# main.net
KiCad netlist of a schematic drawn in Altium Designer
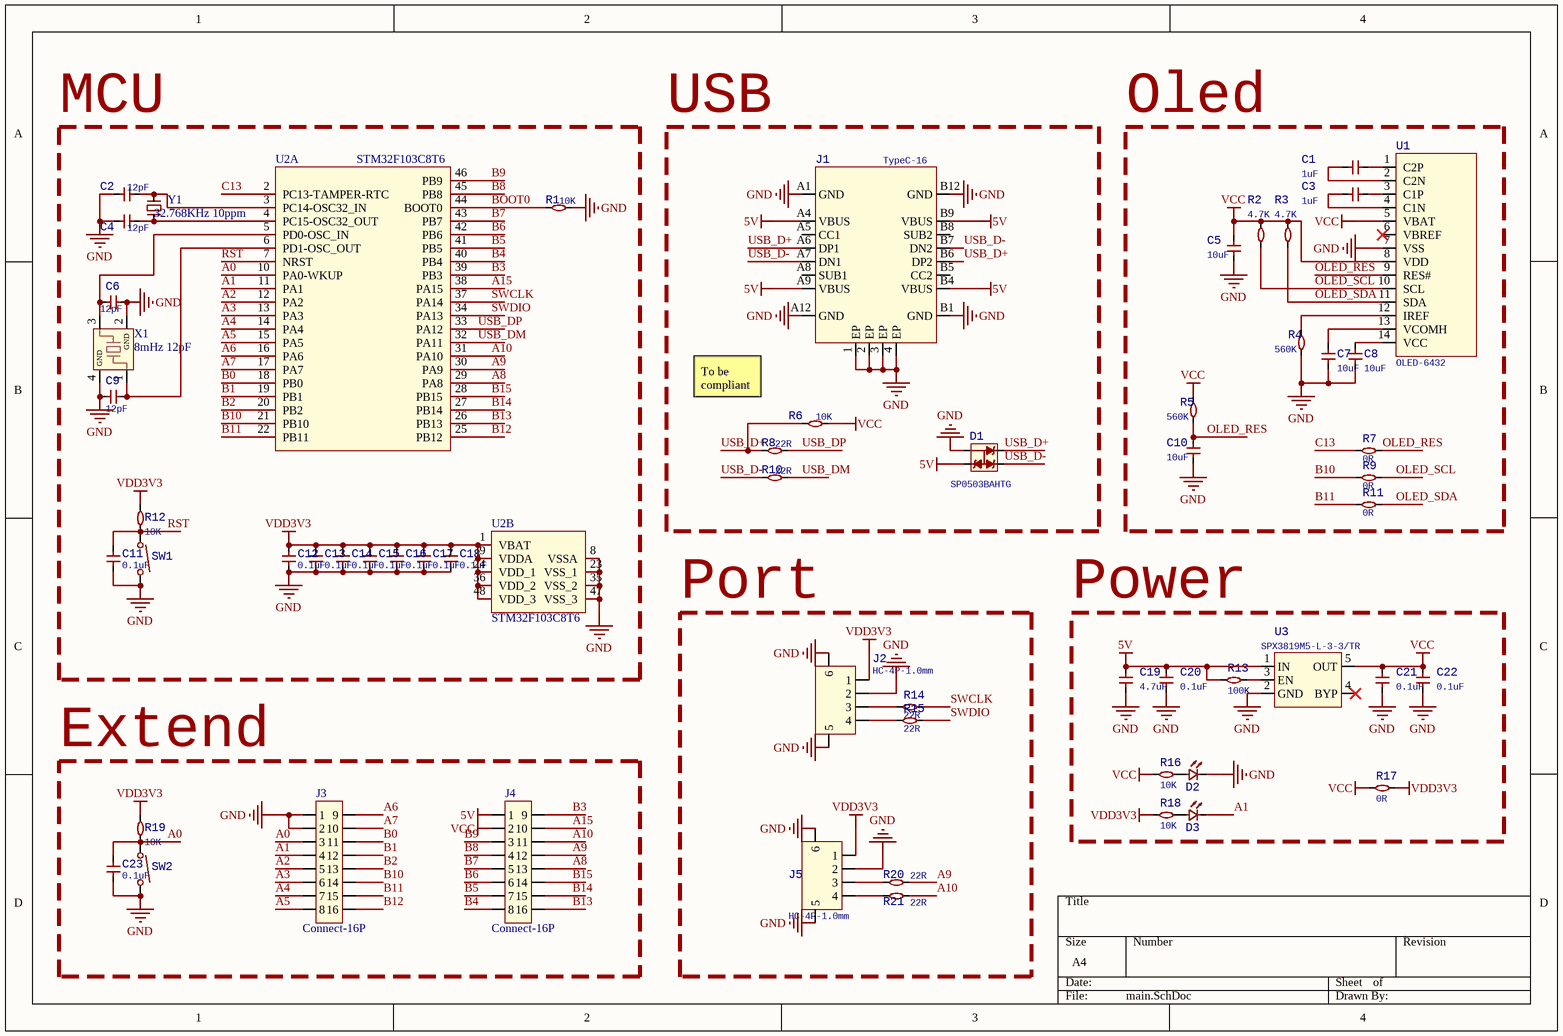
[diagram p0: main.SchDoc]

(export (version "E")
  (design (tool "Eeschema 10.0.6"))
  (components
    (comp (ref "C1")
      (value "1uF")
      (footprint "C0402")
      (description "贴片电容")
      (fields
        (field (name "MANUFACTURER") "SAMSUNG(三星)")
        (field (name "MANUFACTURER PART") "CL05A105KP5NNND")
      )
      (libsource (lib "schLibrary") (part "CAP"))
    )
    (comp (ref "C2")
      (value "12pF")
      (footprint "C0402")
      (description "贴片电容")
      (fields
        (field (name "MANUFACTURER") "SAMSUNG(三星)")
        (field (name "MANUFACTURER PART") "CL05A105KP5NNND")
      )
      (libsource (lib "schLibrary") (part "CAP"))
    )
    (comp (ref "C3")
      (value "1uF")
      (footprint "C0402")
      (description "贴片电容")
      (fields
        (field (name "MANUFACTURER") "SAMSUNG(三星)")
        (field (name "MANUFACTURER PART") "CL05A105KP5NNND")
      )
      (libsource (lib "schLibrary") (part "CAP"))
    )
    (comp (ref "C4")
      (value "12pF")
      (footprint "C0402")
      (description "贴片电容")
      (fields
        (field (name "MANUFACTURER") "SAMSUNG(三星)")
        (field (name "MANUFACTURER PART") "CL05A105KP5NNND")
      )
      (libsource (lib "schLibrary") (part "CAP"))
    )
    (comp (ref "C5")
      (value "10uF")
      (footprint "C0402")
      (description "贴片电容")
      (fields
        (field (name "MANUFACTURER") "SAMSUNG(三星)")
        (field (name "MANUFACTURER PART") "CL05A105KP5NNND")
      )
      (libsource (lib "schLibrary") (part "CAP"))
    )
    (comp (ref "C6")
      (value "12pF")
      (footprint "C0402")
      (description "贴片电容")
      (fields
        (field (name "MANUFACTURER") "SAMSUNG(三星)")
        (field (name "MANUFACTURER PART") "CL05A105KP5NNND")
      )
      (libsource (lib "schLibrary") (part "CAP"))
    )
    (comp (ref "C7")
      (value "10uF")
      (footprint "C0402")
      (description "贴片电容")
      (fields
        (field (name "MANUFACTURER") "SAMSUNG(三星)")
        (field (name "MANUFACTURER PART") "CL05A105KP5NNND")
      )
      (libsource (lib "schLibrary") (part "CAP"))
    )
    (comp (ref "C8")
      (value "10uF")
      (footprint "C0402")
      (description "贴片电容")
      (fields
        (field (name "MANUFACTURER") "SAMSUNG(三星)")
        (field (name "MANUFACTURER PART") "CL05A105KP5NNND")
      )
      (libsource (lib "schLibrary") (part "CAP"))
    )
    (comp (ref "C9")
      (value "12pF")
      (footprint "C0402")
      (description "贴片电容")
      (fields
        (field (name "MANUFACTURER") "SAMSUNG(三星)")
        (field (name "MANUFACTURER PART") "CL05A105KP5NNND")
      )
      (libsource (lib "schLibrary") (part "CAP"))
    )
    (comp (ref "C10")
      (value "10uF")
      (footprint "C0402")
      (description "贴片电容")
      (fields
        (field (name "MANUFACTURER") "SAMSUNG(三星)")
        (field (name "MANUFACTURER PART") "CL05A105KP5NNND")
      )
      (libsource (lib "schLibrary") (part "CAP"))
    )
    (comp (ref "C11")
      (value "0.1uF")
      (footprint "C0402")
      (description "贴片电容")
      (fields
        (field (name "MANUFACTURER") "SAMSUNG(三星)")
        (field (name "MANUFACTURER PART") "CL05A105KP5NNND")
      )
      (libsource (lib "schLibrary") (part "CAP"))
    )
    (comp (ref "C12")
      (value "0.1uF")
      (footprint "C0402")
      (description "贴片电容")
      (fields
        (field (name "MANUFACTURER") "SAMSUNG(三星)")
        (field (name "MANUFACTURER PART") "CL05A105KP5NNND")
      )
      (libsource (lib "schLibrary") (part "CAP"))
    )
    (comp (ref "C13")
      (value "0.1uF")
      (footprint "C0402")
      (description "贴片电容")
      (fields
        (field (name "MANUFACTURER") "SAMSUNG(三星)")
        (field (name "MANUFACTURER PART") "CL05A105KP5NNND")
      )
      (libsource (lib "schLibrary") (part "CAP"))
    )
    (comp (ref "C14")
      (value "0.1uF")
      (footprint "C0402")
      (description "贴片电容")
      (fields
        (field (name "MANUFACTURER") "SAMSUNG(三星)")
        (field (name "MANUFACTURER PART") "CL05A105KP5NNND")
      )
      (libsource (lib "schLibrary") (part "CAP"))
    )
    (comp (ref "C15")
      (value "0.1uF")
      (footprint "C0402")
      (description "贴片电容")
      (fields
        (field (name "MANUFACTURER") "SAMSUNG(三星)")
        (field (name "MANUFACTURER PART") "CL05A105KP5NNND")
      )
      (libsource (lib "schLibrary") (part "CAP"))
    )
    (comp (ref "C16")
      (value "0.1uF")
      (footprint "C0402")
      (description "贴片电容")
      (fields
        (field (name "MANUFACTURER") "SAMSUNG(三星)")
        (field (name "MANUFACTURER PART") "CL05A105KP5NNND")
      )
      (libsource (lib "schLibrary") (part "CAP"))
    )
    (comp (ref "C17")
      (value "0.1uF")
      (footprint "C0402")
      (description "贴片电容")
      (fields
        (field (name "MANUFACTURER") "SAMSUNG(三星)")
        (field (name "MANUFACTURER PART") "CL05A105KP5NNND")
      )
      (libsource (lib "schLibrary") (part "CAP"))
    )
    (comp (ref "C18")
      (value "0.1uF")
      (footprint "C0402")
      (description "贴片电容")
      (fields
        (field (name "MANUFACTURER") "SAMSUNG(三星)")
        (field (name "MANUFACTURER PART") "CL05A105KP5NNND")
      )
      (libsource (lib "schLibrary") (part "CAP"))
    )
    (comp (ref "C19")
      (value "4.7uF")
      (footprint "C0402")
      (description "贴片电容")
      (fields
        (field (name "MANUFACTURER") "SAMSUNG(三星)")
        (field (name "MANUFACTURER PART") "CL05A105KP5NNND")
      )
      (libsource (lib "schLibrary") (part "CAP"))
    )
    (comp (ref "C20")
      (value "0.1uF")
      (footprint "C0402")
      (description "贴片电容")
      (fields
        (field (name "MANUFACTURER") "SAMSUNG(三星)")
        (field (name "MANUFACTURER PART") "CL05A105KP5NNND")
      )
      (libsource (lib "schLibrary") (part "CAP"))
    )
    (comp (ref "C21")
      (value "0.1uF")
      (footprint "C0402")
      (description "贴片电容")
      (fields
        (field (name "MANUFACTURER") "SAMSUNG(三星)")
        (field (name "MANUFACTURER PART") "CL05A105KP5NNND")
      )
      (libsource (lib "schLibrary") (part "CAP"))
    )
    (comp (ref "C22")
      (value "0.1uF")
      (footprint "C0402")
      (description "贴片电容")
      (fields
        (field (name "MANUFACTURER") "SAMSUNG(三星)")
        (field (name "MANUFACTURER PART") "CL05A105KP5NNND")
      )
      (libsource (lib "schLibrary") (part "CAP"))
    )
    (comp (ref "C23")
      (value "0.1uF")
      (footprint "C0402")
      (description "贴片电容")
      (fields
        (field (name "MANUFACTURER") "SAMSUNG(三星)")
        (field (name "MANUFACTURER PART") "CL05A105KP5NNND")
      )
      (libsource (lib "schLibrary") (part "CAP"))
    )
    (comp (ref "D1")
      (value "SP0503BAHTG")
      (footprint "SOT-143")
      (description "USB-三组 瞬态移植二极管")
      (libsource (lib "schLibrary") (part "SP0503BAHTG"))
    )
    (comp (ref "D2")
      (value "LED")
      (footprint "LED-0402")
      (description "贴片发光二极管")
      (fields
        (field (name "MANUFACTURER") "SAMSUNG(三星)")
        (field (name "MANUFACTURER PART") "CL05A105KP5NNND")
      )
      (libsource (lib "schLibrary") (part "LED"))
    )
    (comp (ref "D3")
      (value "LED")
      (footprint "LED-0402")
      (description "贴片发光二极管")
      (fields
        (field (name "MANUFACTURER") "SAMSUNG(三星)")
        (field (name "MANUFACTURER PART") "CL05A105KP5NNND")
      )
      (libsource (lib "schLibrary") (part "LED"))
    )
    (comp (ref "J1")
      (value "TypeC-16")
      (footprint "USB-SMD_TYPE-C-16P")
      (description "Type-C母座; 触点数量:16")
      (fields
        (field (name "MANUFACTURER") "kinghelm(金航标)")
        (field (name "MANUFACTURER PART") "KH-TYPE-C-16P")
      )
      (libsource (lib "schLibrary") (part "TypeC-16P"))
    )
    (comp (ref "J2")
      (value "HC-4P-1.0mm")
      (footprint "SMD_4P_HC-1.0")
      (description "线对板连接器")
      (libsource (lib "schLibrary") (part "HC-4P-1.0mm"))
    )
    (comp (ref "J3")
      (value "Connect-16P")
      (footprint "PIN-16P")
      (description "通用连接器")
      (libsource (lib "schLibrary") (part "Connect-16P"))
    )
    (comp (ref "J4")
      (value "Connect-16P")
      (footprint "PIN-16P")
      (description "通用连接器")
      (libsource (lib "schLibrary") (part "Connect-16P"))
    )
    (comp (ref "J5")
      (value "HC-4P-1.0mm")
      (footprint "SMD_4P_HC-1.0")
      (description "线对板连接器")
      (libsource (lib "schLibrary") (part "HC-4P-1.0mm"))
    )
    (comp (ref "R1")
      (value "10K")
      (footprint "R0402")
      (description "贴片电阻")
      (fields
        (field (name "MANUFACTURER") "UNI-ROYAL(厚声)")
        (field (name "MANUFACTURER PART") "0402WGF1001TCE")
      )
      (libsource (lib "schLibrary") (part "RES"))
    )
    (comp (ref "R2")
      (value "4.7K")
      (footprint "R0402")
      (description "贴片电阻")
      (fields
        (field (name "MANUFACTURER") "UNI-ROYAL(厚声)")
        (field (name "MANUFACTURER PART") "0402WGF1001TCE")
      )
      (libsource (lib "schLibrary") (part "RES"))
    )
    (comp (ref "R3")
      (value "4.7K")
      (footprint "R0402")
      (description "贴片电阻")
      (fields
        (field (name "MANUFACTURER") "UNI-ROYAL(厚声)")
        (field (name "MANUFACTURER PART") "0402WGF1001TCE")
      )
      (libsource (lib "schLibrary") (part "RES"))
    )
    (comp (ref "R4")
      (value "560K")
      (footprint "R0402")
      (description "贴片电阻")
      (fields
        (field (name "MANUFACTURER") "UNI-ROYAL(厚声)")
        (field (name "MANUFACTURER PART") "0402WGF1001TCE")
      )
      (libsource (lib "schLibrary") (part "RES"))
    )
    (comp (ref "R5")
      (value "560K")
      (footprint "R0402")
      (description "贴片电阻")
      (fields
        (field (name "MANUFACTURER") "UNI-ROYAL(厚声)")
        (field (name "MANUFACTURER PART") "0402WGF1001TCE")
      )
      (libsource (lib "schLibrary") (part "RES"))
    )
    (comp (ref "R6")
      (value "10K")
      (footprint "R0402")
      (description "贴片电阻")
      (fields
        (field (name "MANUFACTURER") "UNI-ROYAL(厚声)")
        (field (name "MANUFACTURER PART") "0402WGF1001TCE")
      )
      (libsource (lib "schLibrary") (part "RES"))
    )
    (comp (ref "R7")
      (value "0R")
      (footprint "R0402")
      (description "贴片电阻")
      (fields
        (field (name "MANUFACTURER") "UNI-ROYAL(厚声)")
        (field (name "MANUFACTURER PART") "0402WGF1001TCE")
      )
      (libsource (lib "schLibrary") (part "RES"))
    )
    (comp (ref "R8")
      (value "22R")
      (footprint "R0402")
      (description "贴片电阻")
      (fields
        (field (name "MANUFACTURER") "UNI-ROYAL(厚声)")
        (field (name "MANUFACTURER PART") "0402WGF1001TCE")
      )
      (libsource (lib "schLibrary") (part "RES"))
    )
    (comp (ref "R9")
      (value "0R")
      (footprint "R0402")
      (description "贴片电阻")
      (fields
        (field (name "MANUFACTURER") "UNI-ROYAL(厚声)")
        (field (name "MANUFACTURER PART") "0402WGF1001TCE")
      )
      (libsource (lib "schLibrary") (part "RES"))
    )
    (comp (ref "R10")
      (value "22R")
      (footprint "R0402")
      (description "贴片电阻")
      (fields
        (field (name "MANUFACTURER") "UNI-ROYAL(厚声)")
        (field (name "MANUFACTURER PART") "0402WGF1001TCE")
      )
      (libsource (lib "schLibrary") (part "RES"))
    )
    (comp (ref "R11")
      (value "0R")
      (footprint "R0402")
      (description "贴片电阻")
      (fields
        (field (name "MANUFACTURER") "UNI-ROYAL(厚声)")
        (field (name "MANUFACTURER PART") "0402WGF1001TCE")
      )
      (libsource (lib "schLibrary") (part "RES"))
    )
    (comp (ref "R12")
      (value "10K")
      (footprint "R0402")
      (description "贴片电阻")
      (fields
        (field (name "MANUFACTURER") "UNI-ROYAL(厚声)")
        (field (name "MANUFACTURER PART") "0402WGF1001TCE")
      )
      (libsource (lib "schLibrary") (part "RES"))
    )
    (comp (ref "R13")
      (value "100K")
      (footprint "R0402")
      (description "贴片电阻")
      (fields
        (field (name "MANUFACTURER") "UNI-ROYAL(厚声)")
        (field (name "MANUFACTURER PART") "0402WGF1001TCE")
      )
      (libsource (lib "schLibrary") (part "RES"))
    )
    (comp (ref "R14")
      (value "22R")
      (footprint "R0402")
      (description "贴片电阻")
      (fields
        (field (name "MANUFACTURER") "UNI-ROYAL(厚声)")
        (field (name "MANUFACTURER PART") "0402WGF1001TCE")
      )
      (libsource (lib "schLibrary") (part "RES"))
    )
    (comp (ref "R15")
      (value "22R")
      (footprint "R0402")
      (description "贴片电阻")
      (fields
        (field (name "MANUFACTURER") "UNI-ROYAL(厚声)")
        (field (name "MANUFACTURER PART") "0402WGF1001TCE")
      )
      (libsource (lib "schLibrary") (part "RES"))
    )
    (comp (ref "R16")
      (value "10K")
      (footprint "R0402")
      (description "贴片电阻")
      (fields
        (field (name "MANUFACTURER") "UNI-ROYAL(厚声)")
        (field (name "MANUFACTURER PART") "0402WGF1001TCE")
      )
      (libsource (lib "schLibrary") (part "RES"))
    )
    (comp (ref "R17")
      (value "0R")
      (footprint "R0402")
      (description "贴片电阻")
      (fields
        (field (name "MANUFACTURER") "UNI-ROYAL(厚声)")
        (field (name "MANUFACTURER PART") "0402WGF1001TCE")
      )
      (libsource (lib "schLibrary") (part "RES"))
    )
    (comp (ref "R18")
      (value "10K")
      (footprint "R0402")
      (description "贴片电阻")
      (fields
        (field (name "MANUFACTURER") "UNI-ROYAL(厚声)")
        (field (name "MANUFACTURER PART") "0402WGF1001TCE")
      )
      (libsource (lib "schLibrary") (part "RES"))
    )
    (comp (ref "R19")
      (value "10K")
      (footprint "R0402")
      (description "贴片电阻")
      (fields
        (field (name "MANUFACTURER") "UNI-ROYAL(厚声)")
        (field (name "MANUFACTURER PART") "0402WGF1001TCE")
      )
      (libsource (lib "schLibrary") (part "RES"))
    )
    (comp (ref "R20")
      (value "22R")
      (footprint "R0402")
      (description "贴片电阻")
      (fields
        (field (name "MANUFACTURER") "UNI-ROYAL(厚声)")
        (field (name "MANUFACTURER PART") "0402WGF1001TCE")
      )
      (libsource (lib "schLibrary") (part "RES"))
    )
    (comp (ref "R21")
      (value "22R")
      (footprint "R0402")
      (description "贴片电阻")
      (fields
        (field (name "MANUFACTURER") "UNI-ROYAL(厚声)")
        (field (name "MANUFACTURER PART") "0402WGF1001TCE")
      )
      (libsource (lib "schLibrary") (part "RES"))
    )
    (comp (ref "SW1")
      (value "3*4两脚按键")
      (footprint "SW-SMD_L4.0-W2.9")
      (description "3*4两脚贴片不带柱")
      (fields
        (field (name "MANUFACTURER") "BRIGHT(博瑞泰)")
        (field (name "MANUFACTURER PART") "TSA343G00-250J2")
      )
      (libsource (lib "schLibrary") (part "Switch"))
    )
    (comp (ref "SW2")
      (value "3*4两脚按键")
      (footprint "SW-SMD_L4.0-W2.9")
      (description "3*4两脚贴片不带柱")
      (fields
        (field (name "MANUFACTURER") "BRIGHT(博瑞泰)")
        (field (name "MANUFACTURER PART") "TSA343G00-250J2")
      )
      (libsource (lib "schLibrary") (part "Switch"))
    )
    (comp (ref "U1")
      (value "OLED-6432")
      (footprint "OLED-0.96-128x64")
      (libsource (lib "schLibrary") (part "OLED"))
    )
    (comp (ref "U2")
      (value "STM32F103C8T6")
      (footprint "LQFP-48_L7.0-W7.0-P0.50")
      (description "CPU最大主频：72MHz\r\nRAM：20KB \r\nFLASH：64KB")
      (libsource (lib "schLibrary") (part "STM32F103C8T6"))
    )
    (comp (ref "U3")
      (value "SPX3819M5-L-3-3/TR")
      (footprint "SOT-23-5")
      (description "LDO输入电压:16V;输出电压:3.3V")
      (fields (field (name "MANUFACTURER") "MaxLinear"))
      (libsource (lib "schLibrary") (part "SPX3819M5-L-3-3/TR"))
    )
    (comp (ref "X1")
      (value "8mHz 12pF")
      (footprint "SMD2016-4P")
      (description "无源晶振  频率公差：±10ppm")
      (libsource (lib "schLibrary") (part "XTAL"))
    )
    (comp (ref "Y1")
      (value "32.768KHz 10ppm")
      (footprint "SMD_2012-2P")
      (description "无源晶振  频率公差：±10ppm")
      (libsource (lib "schLibrary") (part "XTAL-2P"))
    )
  )
  (nets
    (net (code "1") (name "/A0") (class "Default")
      (node (ref "C23") (pin "2") (pinfunction "2_2") (pintype "passive"))
      (node (ref "J3") (pin "3") (pinfunction "3_3") (pintype "passive"))
      (node (ref "R19") (pin "1") (pinfunction "1_1") (pintype "passive"))
      (node (ref "SW2") (pin "1") (pinfunction "1_1") (pintype "passive"))
      (node (ref "U2") (pin "10") (pinfunction "PA0-WKUP_10") (pintype "passive"))
    )
    (net (code "2") (name "/A1") (class "Default")
      (node (ref "D3") (pin "1") (pinfunction "1_1") (pintype "passive"))
      (node (ref "J3") (pin "4") (pinfunction "4_4") (pintype "passive"))
      (node (ref "U2") (pin "11") (pinfunction "PA1_11") (pintype "passive"))
    )
    (net (code "3") (name "/A2") (class "Default")
      (node (ref "J3") (pin "5") (pinfunction "5_5") (pintype "passive"))
      (node (ref "U2") (pin "12") (pinfunction "PA2_12") (pintype "passive"))
    )
    (net (code "4") (name "/A3") (class "Default")
      (node (ref "J3") (pin "6") (pinfunction "6_6") (pintype "passive"))
      (node (ref "U2") (pin "13") (pinfunction "PA3_13") (pintype "passive"))
    )
    (net (code "5") (name "/A4") (class "Default")
      (node (ref "J3") (pin "7") (pinfunction "7_7") (pintype "passive"))
      (node (ref "U2") (pin "14") (pinfunction "PA4_14") (pintype "passive"))
    )
    (net (code "6") (name "/A5") (class "Default")
      (node (ref "J3") (pin "8") (pinfunction "8_8") (pintype "passive"))
      (node (ref "U2") (pin "15") (pinfunction "PA5_15") (pintype "passive"))
    )
    (net (code "7") (name "/A6") (class "Default")
      (node (ref "J3") (pin "9") (pinfunction "9_9") (pintype "passive"))
      (node (ref "U2") (pin "16") (pinfunction "PA6_16") (pintype "passive"))
    )
    (net (code "8") (name "/A7") (class "Default")
      (node (ref "J3") (pin "10") (pinfunction "10_10") (pintype "passive"))
      (node (ref "U2") (pin "17") (pinfunction "PA7_17") (pintype "passive"))
    )
    (net (code "9") (name "/A8") (class "Default")
      (node (ref "J4") (pin "13") (pinfunction "13_13") (pintype "passive"))
      (node (ref "U2") (pin "29") (pinfunction "PA8_29") (pintype "passive"))
    )
    (net (code "10") (name "/A9") (class "Default")
      (node (ref "J4") (pin "12") (pinfunction "12_12") (pintype "passive"))
      (node (ref "R20") (pin "2") (pinfunction "2_2") (pintype "passive"))
      (node (ref "U2") (pin "30") (pinfunction "PA9_30") (pintype "passive"))
    )
    (net (code "11") (name "/A10") (class "Default")
      (node (ref "J4") (pin "11") (pinfunction "11_11") (pintype "passive"))
      (node (ref "R21") (pin "2") (pinfunction "2_2") (pintype "passive"))
      (node (ref "U2") (pin "31") (pinfunction "PA10_31") (pintype "passive"))
    )
    (net (code "12") (name "/A15") (class "Default")
      (node (ref "J4") (pin "10") (pinfunction "10_10") (pintype "passive"))
      (node (ref "U2") (pin "38") (pinfunction "PA15_38") (pintype "passive"))
    )
    (net (code "13") (name "/B0") (class "Default")
      (node (ref "J3") (pin "11") (pinfunction "11_11") (pintype "passive"))
      (node (ref "U2") (pin "18") (pinfunction "PB0_18") (pintype "passive"))
    )
    (net (code "14") (name "/B1") (class "Default")
      (node (ref "J3") (pin "12") (pinfunction "12_12") (pintype "passive"))
      (node (ref "U2") (pin "19") (pinfunction "PB1_19") (pintype "passive"))
    )
    (net (code "15") (name "/B2") (class "Default")
      (node (ref "J3") (pin "13") (pinfunction "13_13") (pintype "passive"))
      (node (ref "U2") (pin "20") (pinfunction "PB2_20") (pintype "passive"))
    )
    (net (code "16") (name "/B3") (class "Default")
      (node (ref "J4") (pin "9") (pinfunction "9_9") (pintype "passive"))
      (node (ref "U2") (pin "39") (pinfunction "PB3_39") (pintype "passive"))
    )
    (net (code "17") (name "/B4") (class "Default")
      (node (ref "J4") (pin "8") (pinfunction "8_8") (pintype "passive"))
      (node (ref "U2") (pin "40") (pinfunction "PB4_40") (pintype "passive"))
    )
    (net (code "18") (name "/B5") (class "Default")
      (node (ref "J4") (pin "7") (pinfunction "7_7") (pintype "passive"))
      (node (ref "U2") (pin "41") (pinfunction "PB5_41") (pintype "passive"))
    )
    (net (code "19") (name "/B6") (class "Default")
      (node (ref "J4") (pin "6") (pinfunction "6_6") (pintype "passive"))
      (node (ref "U2") (pin "42") (pinfunction "PB6_42") (pintype "passive"))
    )
    (net (code "20") (name "/B7") (class "Default")
      (node (ref "J4") (pin "5") (pinfunction "5_5") (pintype "passive"))
      (node (ref "U2") (pin "43") (pinfunction "PB7_43") (pintype "passive"))
    )
    (net (code "21") (name "/B8") (class "Default")
      (node (ref "J4") (pin "4") (pinfunction "4_4") (pintype "passive"))
      (node (ref "U2") (pin "45") (pinfunction "PB8_45") (pintype "passive"))
    )
    (net (code "22") (name "/B9") (class "Default")
      (node (ref "J4") (pin "3") (pinfunction "3_3") (pintype "passive"))
      (node (ref "U2") (pin "46") (pinfunction "PB9_46") (pintype "passive"))
    )
    (net (code "23") (name "/B10") (class "Default")
      (node (ref "J3") (pin "14") (pinfunction "14_14") (pintype "passive"))
      (node (ref "R9") (pin "2") (pinfunction "2_2") (pintype "passive"))
      (node (ref "U2") (pin "21") (pinfunction "PB10_21") (pintype "passive"))
    )
    (net (code "24") (name "/B11") (class "Default")
      (node (ref "J3") (pin "15") (pinfunction "15_15") (pintype "passive"))
      (node (ref "R11") (pin "2") (pinfunction "2_2") (pintype "passive"))
      (node (ref "U2") (pin "22") (pinfunction "PB11_22") (pintype "passive"))
    )
    (net (code "25") (name "/B12") (class "Default")
      (node (ref "J3") (pin "16") (pinfunction "16_16") (pintype "passive"))
      (node (ref "U2") (pin "25") (pinfunction "PB12_25") (pintype "passive"))
    )
    (net (code "26") (name "/B13") (class "Default")
      (node (ref "J4") (pin "16") (pinfunction "16_16") (pintype "passive"))
      (node (ref "U2") (pin "26") (pinfunction "PB13_26") (pintype "passive"))
    )
    (net (code "27") (name "/B14") (class "Default")
      (node (ref "J4") (pin "15") (pinfunction "15_15") (pintype "passive"))
      (node (ref "U2") (pin "27") (pinfunction "PB14_27") (pintype "passive"))
    )
    (net (code "28") (name "/B15") (class "Default")
      (node (ref "J4") (pin "14") (pinfunction "14_14") (pintype "passive"))
      (node (ref "U2") (pin "28") (pinfunction "PB15_28") (pintype "passive"))
    )
    (net (code "29") (name "/BOOT0") (class "Default")
      (node (ref "R1") (pin "2") (pinfunction "2_2") (pintype "passive"))
      (node (ref "U2") (pin "44") (pinfunction "BOOT0_44") (pintype "passive"))
    )
    (net (code "30") (name "/C13") (class "Default")
      (node (ref "R7") (pin "2") (pinfunction "2_2") (pintype "passive"))
      (node (ref "U2") (pin "2") (pinfunction "PC13-TAMPER-RTC_2") (pintype "passive"))
    )
    (net (code "31") (name "/OLED_RES") (class "Default")
      (node (ref "C10") (pin "1") (pinfunction "1_1") (pintype "passive"))
      (node (ref "R5") (pin "1") (pinfunction "1_1") (pintype "passive"))
      (node (ref "R7") (pin "1") (pinfunction "1_1") (pintype "passive"))
      (node (ref "U1") (pin "9") (pinfunction "RES#_9") (pintype "passive"))
    )
    (net (code "32") (name "/OLED_SCL") (class "Default")
      (node (ref "R2") (pin "1") (pinfunction "1_1") (pintype "passive"))
      (node (ref "R9") (pin "1") (pinfunction "1_1") (pintype "passive"))
      (node (ref "U1") (pin "10") (pinfunction "SCL_10") (pintype "passive"))
    )
    (net (code "33") (name "/OLED_SDA") (class "Default")
      (node (ref "R11") (pin "1") (pinfunction "1_1") (pintype "passive"))
      (node (ref "R3") (pin "1") (pinfunction "1_1") (pintype "passive"))
      (node (ref "U1") (pin "11") (pinfunction "SDA_11") (pintype "passive"))
    )
    (net (code "34") (name "/RST") (class "Default")
      (node (ref "C11") (pin "2") (pinfunction "2_2") (pintype "passive"))
      (node (ref "R12") (pin "1") (pinfunction "1_1") (pintype "passive"))
      (node (ref "SW1") (pin "1") (pinfunction "1_1") (pintype "passive"))
      (node (ref "U2") (pin "7") (pinfunction "NRST_7") (pintype "passive"))
    )
    (net (code "35") (name "/SWCLK") (class "Default")
      (node (ref "R14") (pin "2") (pinfunction "2_2") (pintype "passive"))
      (node (ref "U2") (pin "37") (pinfunction "PA14_37") (pintype "passive"))
    )
    (net (code "36") (name "/SWDIO") (class "Default")
      (node (ref "R15") (pin "2") (pinfunction "2_2") (pintype "passive"))
      (node (ref "U2") (pin "34") (pinfunction "PA13_34") (pintype "passive"))
    )
    (net (code "37") (name "/USB_D+") (class "Default")
      (node (ref "D1") (pin "4") (pinfunction "4_4") (pintype "passive"))
      (node (ref "J1") (pin "A6") (pinfunction "DP1_A6") (pintype "passive"))
      (node (ref "J1") (pin "B6") (pinfunction "DP2_B6") (pintype "passive"))
      (node (ref "R6") (pin "1") (pinfunction "1_1") (pintype "passive"))
      (node (ref "R8") (pin "1") (pinfunction "1_1") (pintype "passive"))
    )
    (net (code "38") (name "/USB_D-") (class "Default")
      (node (ref "D1") (pin "3") (pinfunction "3_3") (pintype "passive"))
      (node (ref "J1") (pin "A7") (pinfunction "DN1_A7") (pintype "passive"))
      (node (ref "J1") (pin "B7") (pinfunction "DN2_B7") (pintype "passive"))
      (node (ref "R10") (pin "1") (pinfunction "1_1") (pintype "passive"))
    )
    (net (code "39") (name "/USB_DM") (class "Default")
      (node (ref "R10") (pin "2") (pinfunction "2_2") (pintype "passive"))
      (node (ref "U2") (pin "32") (pinfunction "PA11_32") (pintype "passive"))
    )
    (net (code "40") (name "/USB_DP") (class "Default")
      (node (ref "R8") (pin "2") (pinfunction "2_2") (pintype "passive"))
      (node (ref "U2") (pin "33") (pinfunction "PA12_33") (pintype "passive"))
    )
    (net (code "41") (name "5V") (class "Default")
      (node (ref "C19") (pin "1") (pinfunction "1_1") (pintype "passive"))
      (node (ref "C20") (pin "1") (pinfunction "1_1") (pintype "passive"))
      (node (ref "D1") (pin "2") (pinfunction "2_2") (pintype "passive"))
      (node (ref "J1") (pin "A4") (pinfunction "VBUS_A4") (pintype "passive"))
      (node (ref "J1") (pin "A9") (pinfunction "VBUS_A9") (pintype "passive"))
      (node (ref "J1") (pin "B4") (pinfunction "VBUS_B4") (pintype "passive"))
      (node (ref "J1") (pin "B9") (pinfunction "VBUS_B9") (pintype "passive"))
      (node (ref "J4") (pin "1") (pinfunction "1_1") (pintype "passive"))
      (node (ref "R13") (pin "2") (pinfunction "2_2") (pintype "passive"))
      (node (ref "U3") (pin "1") (pinfunction "IN_1") (pintype "passive"))
    )
    (net (code "42") (name "GND") (class "Default")
      (node (ref "C10") (pin "2") (pinfunction "2_2") (pintype "passive"))
      (node (ref "C11") (pin "1") (pinfunction "1_1") (pintype "passive"))
      (node (ref "C12") (pin "1") (pinfunction "1_1") (pintype "passive"))
      (node (ref "C13") (pin "1") (pinfunction "1_1") (pintype "passive"))
      (node (ref "C14") (pin "1") (pinfunction "1_1") (pintype "passive"))
      (node (ref "C15") (pin "1") (pinfunction "1_1") (pintype "passive"))
      (node (ref "C16") (pin "1") (pinfunction "1_1") (pintype "passive"))
      (node (ref "C17") (pin "1") (pinfunction "1_1") (pintype "passive"))
      (node (ref "C18") (pin "1") (pinfunction "1_1") (pintype "passive"))
      (node (ref "C19") (pin "2") (pinfunction "2_2") (pintype "passive"))
      (node (ref "C2") (pin "2") (pinfunction "2_2") (pintype "passive"))
      (node (ref "C20") (pin "2") (pinfunction "2_2") (pintype "passive"))
      (node (ref "C21") (pin "2") (pinfunction "2_2") (pintype "passive"))
      (node (ref "C22") (pin "2") (pinfunction "2_2") (pintype "passive"))
      (node (ref "C23") (pin "1") (pinfunction "1_1") (pintype "passive"))
      (node (ref "C4") (pin "2") (pinfunction "2_2") (pintype "passive"))
      (node (ref "C5") (pin "2") (pinfunction "2_2") (pintype "passive"))
      (node (ref "C6") (pin "1") (pinfunction "1_1") (pintype "passive"))
      (node (ref "C7") (pin "2") (pinfunction "2_2") (pintype "passive"))
      (node (ref "C8") (pin "2") (pinfunction "2_2") (pintype "passive"))
      (node (ref "C9") (pin "2") (pinfunction "2_2") (pintype "passive"))
      (node (ref "D1") (pin "1") (pinfunction "1_1") (pintype "passive"))
      (node (ref "D2") (pin "1") (pinfunction "1_1") (pintype "passive"))
      (node (ref "J1") (pin "1") (pinfunction "EP_1") (pintype "passive"))
      (node (ref "J1") (pin "2") (pinfunction "EP_2") (pintype "passive"))
      (node (ref "J1") (pin "3") (pinfunction "EP_3") (pintype "passive"))
      (node (ref "J1") (pin "4") (pinfunction "EP_4") (pintype "passive"))
      (node (ref "J1") (pin "A1") (pinfunction "GND_A1") (pintype "passive"))
      (node (ref "J1") (pin "A12") (pinfunction "GND_A12") (pintype "passive"))
      (node (ref "J1") (pin "B1") (pinfunction "GND_B1") (pintype "passive"))
      (node (ref "J1") (pin "B12") (pinfunction "GND_B12") (pintype "passive"))
      (node (ref "J2") (pin "2") (pinfunction "2_2") (pintype "passive"))
      (node (ref "J2") (pin "5") (pinfunction "5_5") (pintype "passive"))
      (node (ref "J2") (pin "6") (pinfunction "6_6") (pintype "passive"))
      (node (ref "J3") (pin "1") (pinfunction "1_1") (pintype "passive"))
      (node (ref "J3") (pin "2") (pinfunction "2_2") (pintype "passive"))
      (node (ref "J5") (pin "2") (pinfunction "2_2") (pintype "passive"))
      (node (ref "J5") (pin "5") (pinfunction "5_5") (pintype "passive"))
      (node (ref "J5") (pin "6") (pinfunction "6_6") (pintype "passive"))
      (node (ref "R1") (pin "1") (pinfunction "1_1") (pintype "passive"))
      (node (ref "R4") (pin "1") (pinfunction "1_1") (pintype "passive"))
      (node (ref "SW1") (pin "2") (pinfunction "2_2") (pintype "passive"))
      (node (ref "SW2") (pin "2") (pinfunction "2_2") (pintype "passive"))
      (node (ref "U1") (pin "7") (pinfunction "VSS_7") (pintype "passive"))
      (node (ref "U2") (pin "23") (pinfunction "VSS_1_23") (pintype "passive"))
      (node (ref "U2") (pin "35") (pinfunction "VSS_2_35") (pintype "passive"))
      (node (ref "U2") (pin "47") (pinfunction "VSS_3_47") (pintype "passive"))
      (node (ref "U2") (pin "8") (pinfunction "VSSA_8") (pintype "passive"))
      (node (ref "U3") (pin "2") (pinfunction "GND_2") (pintype "passive"))
      (node (ref "X1") (pin "2") (pinfunction "GND_2") (pintype "passive"))
      (node (ref "X1") (pin "4") (pinfunction "GND_4") (pintype "passive"))
    )
    (net (code "43") (name "Net-(D2-Pad2)") (class "Default")
      (node (ref "D2") (pin "2") (pinfunction "2_2") (pintype "passive"))
      (node (ref "R16") (pin "2") (pinfunction "2_2") (pintype "passive"))
    )
    (net (code "44") (name "Net-(D3-Pad2)") (class "Default")
      (node (ref "D3") (pin "2") (pinfunction "2_2") (pintype "passive"))
      (node (ref "R18") (pin "2") (pinfunction "2_2") (pintype "passive"))
    )
    (net (code "45") (name "Net-(J2-Pad3)") (class "Default")
      (node (ref "J2") (pin "3") (pinfunction "3_3") (pintype "passive"))
      (node (ref "R14") (pin "1") (pinfunction "1_1") (pintype "passive"))
    )
    (net (code "46") (name "Net-(J2-Pad4)") (class "Default")
      (node (ref "J2") (pin "4") (pinfunction "4_4") (pintype "passive"))
      (node (ref "R15") (pin "1") (pinfunction "1_1") (pintype "passive"))
    )
    (net (code "47") (name "Net-(J5-Pad3)") (class "Default")
      (node (ref "J5") (pin "3") (pinfunction "3_3") (pintype "passive"))
      (node (ref "R20") (pin "1") (pinfunction "1_1") (pintype "passive"))
    )
    (net (code "48") (name "Net-(J5-Pad4)") (class "Default")
      (node (ref "J5") (pin "4") (pinfunction "4_4") (pintype "passive"))
      (node (ref "R21") (pin "1") (pinfunction "1_1") (pintype "passive"))
    )
    (net (code "49") (name "Net-(U1-C1N)") (class "Default")
      (node (ref "C3") (pin "2") (pinfunction "2_2") (pintype "passive"))
      (node (ref "U1") (pin "4") (pinfunction "C1N_4") (pintype "passive"))
    )
    (net (code "50") (name "Net-(U1-C1P)") (class "Default")
      (node (ref "C3") (pin "1") (pinfunction "1_1") (pintype "passive"))
      (node (ref "U1") (pin "3") (pinfunction "C1P_3") (pintype "passive"))
    )
    (net (code "51") (name "Net-(U1-C2N)") (class "Default")
      (node (ref "C1") (pin "2") (pinfunction "2_2") (pintype "passive"))
      (node (ref "U1") (pin "2") (pinfunction "C2N_2") (pintype "passive"))
    )
    (net (code "52") (name "Net-(U1-C2P)") (class "Default")
      (node (ref "C1") (pin "1") (pinfunction "1_1") (pintype "passive"))
      (node (ref "U1") (pin "1") (pinfunction "C2P_1") (pintype "passive"))
    )
    (net (code "53") (name "Net-(U1-IREF)") (class "Default")
      (node (ref "R4") (pin "2") (pinfunction "2_2") (pintype "passive"))
      (node (ref "U1") (pin "12") (pinfunction "IREF_12") (pintype "passive"))
    )
    (net (code "54") (name "Net-(U1-VCC)") (class "Default")
      (node (ref "C8") (pin "1") (pinfunction "1_1") (pintype "passive"))
      (node (ref "U1") (pin "14") (pinfunction "VCC_14") (pintype "passive"))
    )
    (net (code "55") (name "Net-(U1-VCOMH)") (class "Default")
      (node (ref "C7") (pin "1") (pinfunction "1_1") (pintype "passive"))
      (node (ref "U1") (pin "13") (pinfunction "VCOMH_13") (pintype "passive"))
    )
    (net (code "56") (name "Net-(U2A-PC14-OSC32_IN)") (class "Default")
      (node (ref "C2") (pin "1") (pinfunction "1_1") (pintype "passive"))
      (node (ref "U2") (pin "3") (pinfunction "PC14-OSC32_IN_3") (pintype "passive"))
      (node (ref "Y1") (pin "2") (pinfunction "2_2") (pintype "passive"))
    )
    (net (code "57") (name "Net-(U2A-PC15-OSC32_OUT)") (class "Default")
      (node (ref "C4") (pin "1") (pinfunction "1_1") (pintype "passive"))
      (node (ref "U2") (pin "4") (pinfunction "PC15-OSC32_OUT_4") (pintype "passive"))
      (node (ref "Y1") (pin "1") (pinfunction "1_1") (pintype "passive"))
    )
    (net (code "58") (name "Net-(U2A-PD0-OSC_IN)") (class "Default")
      (node (ref "C6") (pin "2") (pinfunction "2_2") (pintype "passive"))
      (node (ref "U2") (pin "5") (pinfunction "PD0-OSC_IN_5") (pintype "passive"))
      (node (ref "X1") (pin "3") (pinfunction "1_3") (pintype "passive"))
    )
    (net (code "59") (name "Net-(U2A-PD1-OSC_OUT)") (class "Default")
      (node (ref "C9") (pin "1") (pinfunction "1_1") (pintype "passive"))
      (node (ref "U2") (pin "6") (pinfunction "PD1-OSC_OUT_6") (pintype "passive"))
      (node (ref "X1") (pin "1") (pinfunction "1_1") (pintype "passive"))
    )
    (net (code "60") (name "Net-(U3-EN)") (class "Default")
      (node (ref "R13") (pin "1") (pinfunction "1_1") (pintype "passive"))
      (node (ref "U3") (pin "3") (pinfunction "EN_3") (pintype "passive"))
    )
    (net (code "61") (name "VCC") (class "Default")
      (node (ref "C21") (pin "1") (pinfunction "1_1") (pintype "passive"))
      (node (ref "C22") (pin "1") (pinfunction "1_1") (pintype "passive"))
      (node (ref "C5") (pin "1") (pinfunction "1_1") (pintype "passive"))
      (node (ref "J4") (pin "2") (pinfunction "2_2") (pintype "passive"))
      (node (ref "R16") (pin "1") (pinfunction "1_1") (pintype "passive"))
      (node (ref "R17") (pin "1") (pinfunction "1_1") (pintype "passive"))
      (node (ref "R2") (pin "2") (pinfunction "2_2") (pintype "passive"))
      (node (ref "R3") (pin "2") (pinfunction "2_2") (pintype "passive"))
      (node (ref "R5") (pin "2") (pinfunction "2_2") (pintype "passive"))
      (node (ref "R6") (pin "2") (pinfunction "2_2") (pintype "passive"))
      (node (ref "U1") (pin "5") (pinfunction "VBAT_5") (pintype "passive"))
      (node (ref "U1") (pin "8") (pinfunction "VDD_8") (pintype "passive"))
      (node (ref "U3") (pin "5") (pinfunction "OUT_5") (pintype "passive"))
    )
    (net (code "62") (name "VDD3V3") (class "Default")
      (node (ref "C12") (pin "2") (pinfunction "2_2") (pintype "passive"))
      (node (ref "C13") (pin "2") (pinfunction "2_2") (pintype "passive"))
      (node (ref "C14") (pin "2") (pinfunction "2_2") (pintype "passive"))
      (node (ref "C15") (pin "2") (pinfunction "2_2") (pintype "passive"))
      (node (ref "C16") (pin "2") (pinfunction "2_2") (pintype "passive"))
      (node (ref "C17") (pin "2") (pinfunction "2_2") (pintype "passive"))
      (node (ref "C18") (pin "2") (pinfunction "2_2") (pintype "passive"))
      (node (ref "J2") (pin "1") (pinfunction "1_1") (pintype "passive"))
      (node (ref "J5") (pin "1") (pinfunction "1_1") (pintype "passive"))
      (node (ref "R12") (pin "2") (pinfunction "2_2") (pintype "passive"))
      (node (ref "R17") (pin "2") (pinfunction "2_2") (pintype "passive"))
      (node (ref "R18") (pin "1") (pinfunction "1_1") (pintype "passive"))
      (node (ref "R19") (pin "2") (pinfunction "2_2") (pintype "passive"))
      (node (ref "U2") (pin "1") (pinfunction "VBAT_1") (pintype "passive"))
      (node (ref "U2") (pin "24") (pinfunction "VDD_1_24") (pintype "passive"))
      (node (ref "U2") (pin "36") (pinfunction "VDD_2_36") (pintype "passive"))
      (node (ref "U2") (pin "48") (pinfunction "VDD_3_48") (pintype "passive"))
      (node (ref "U2") (pin "9") (pinfunction "VDDA_9") (pintype "passive"))
    )
    (net (code "63") (name "unconnected-(J1-CC1-PadA5)") (class "Default")
      (node (ref "J1") (pin "A5") (pinfunction "CC1_A5") (pintype "passive"))
    )
    (net (code "64") (name "unconnected-(J1-CC2-PadB5)") (class "Default")
      (node (ref "J1") (pin "B5") (pinfunction "CC2_B5") (pintype "passive"))
    )
    (net (code "65") (name "unconnected-(J1-SUB1-PadA8)") (class "Default")
      (node (ref "J1") (pin "A8") (pinfunction "SUB1_A8") (pintype "passive"))
    )
    (net (code "66") (name "unconnected-(J1-SUB2-PadB8)") (class "Default")
      (node (ref "J1") (pin "B8") (pinfunction "SUB2_B8") (pintype "passive"))
    )
    (net (code "67") (name "unconnected-(U1-VBREF-Pad6)") (class "Default")
      (node (ref "U1") (pin "6") (pinfunction "VBREF_6") (pintype "passive+no_connect"))
    )
    (net (code "68") (name "unconnected-(U3-BYP-Pad4)") (class "Default")
      (node (ref "U3") (pin "4") (pinfunction "BYP_4") (pintype "passive+no_connect"))
    )
  )
)
